# FTDI_USB_UART.net
KiCad netlist of a schematic drawn in Altium Designer
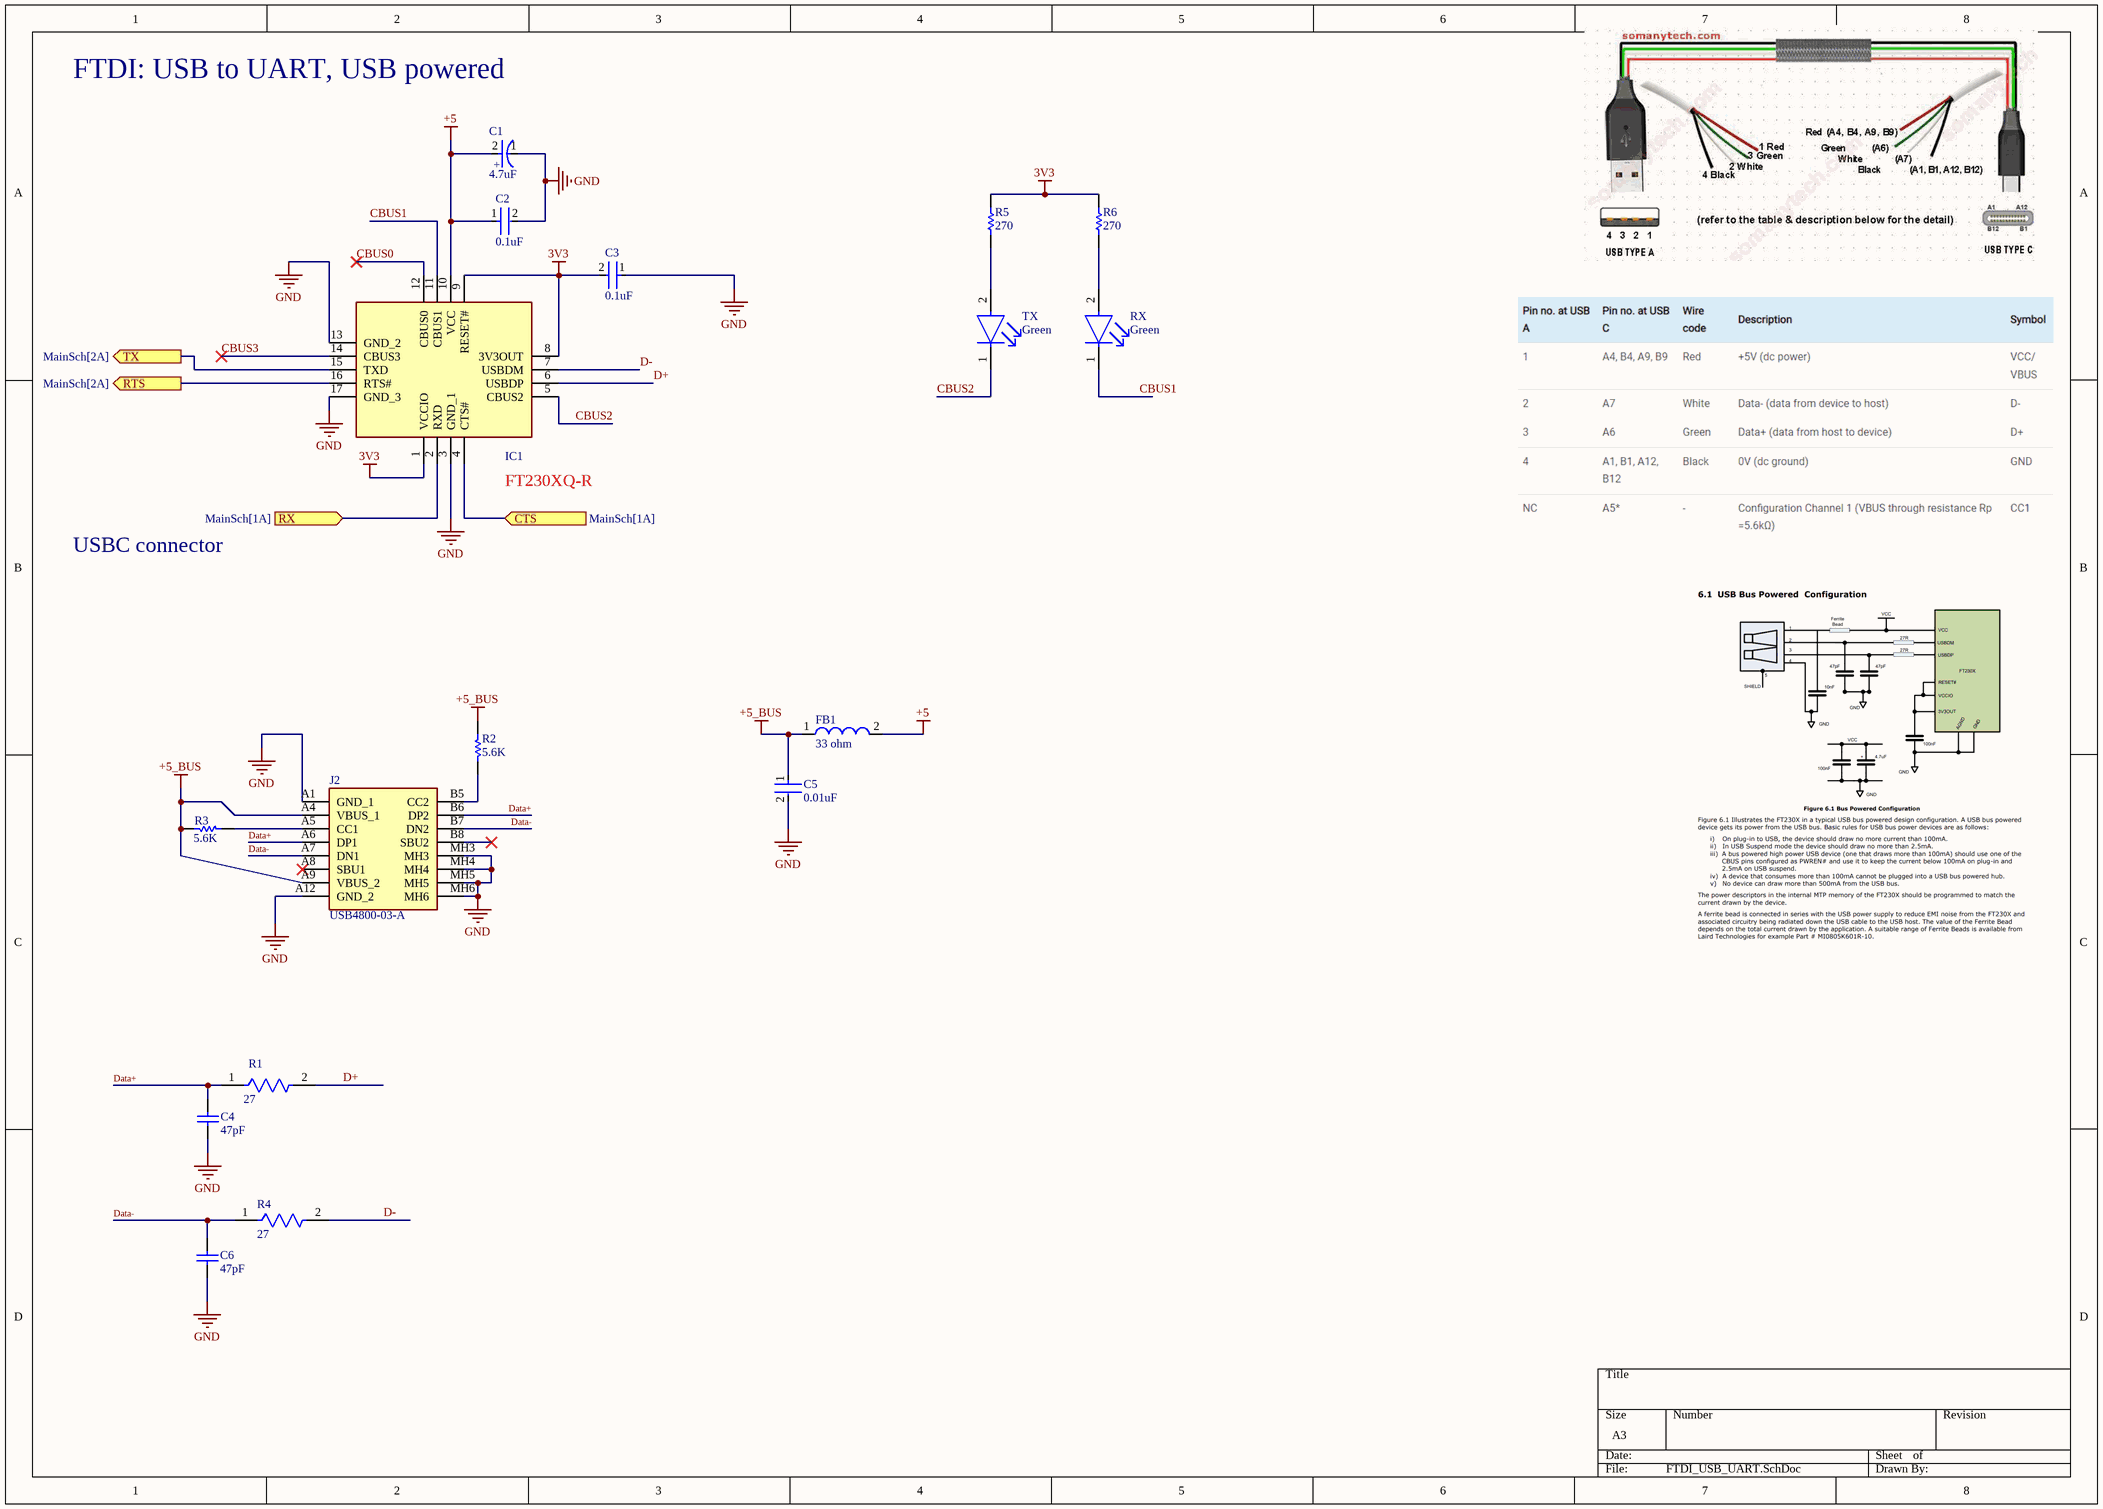
[diagram p0: FTDI_USB_UART.SchDoc]

(export (version "E")
  (design (tool "Eeschema 10.0.6"))
  (components
    (comp (ref "C1")
      (value "4.7uF")
      (footprint "FP-RAD-TH-D_6_3_0_5-L_11-MFG")
      (description "Aluminum Electrolytic Capacitors (Radial Lead Type) 4.7uF ±20% 160V")
      (fields (field (name "VOLTAGE") "160V") (field (name "TOLERANCE") "20%"))
      (libsource (lib "Altium Content Vault") (part "203bc49f2ac43e59fd269a8c329ed05"))
    )
    (comp (ref "C2")
      (value "0.1uF")
      (footprint "FP-C0603C-CF-MFG")
      (description "CAP CER 0.1UF 50V X7R 0603")
      (fields (field (name "TOLERANCE") "0.1") (field (name "MANUFACTURER") "KEMET"))
      (libsource (lib "Altium Content Vault") (part "b4654b650e69147ec39a6b967a45e02"))
    )
    (comp (ref "C3")
      (value "0.1uF")
      (footprint "FP-C0603C-CF-MFG")
      (description "CAP CER 0.1UF 50V X7R 0603")
      (fields (field (name "TOLERANCE") "0.1") (field (name "MANUFACTURER") "KEMET"))
      (libsource (lib "Altium Content Vault") (part "b4654b650e69147ec39a6b967a45e02"))
    )
    (comp (ref "C4")
      (value "47pF")
      (footprint "CAPC1608X90X35NL10T15")
      (fields (field (name "MANUFACTURER") "Murata") (field (name "PART NUMBER") "GRM1885C1H470JA01D"))
      (libsource (lib "Altium Content Vault") (part "CAP"))
    )
    (comp (ref "C5")
      (value "0.01uF")
      (footprint "FP-CC0603-DA-MFG")
      (description "CAP CER 10000PF 50V X7R 0603")
      (fields (field (name "TOLERANCE") "0.1") (field (name "MANUFACTURER PART NUMBER") "CC0603KRX7R9BB103"))
      (libsource (lib "Altium Content Vault") (part "11868f565c42a9108669ba33697ecf6"))
    )
    (comp (ref "C6")
      (value "47pF")
      (footprint "CAPC1608X90X35NL10T15")
      (fields (field (name "MANUFACTURER") "Murata") (field (name "PART NUMBER") "GRM1885C1H470JA01D"))
      (libsource (lib "Altium Content Vault") (part "CAP"))
    )
    (comp (ref "FB1")
      (value "33 ohm")
      (footprint "SMD-0805")
      (description "SMD EMI Suppression Ferrite Bead WE-CBF, Z = 33 Ohm")
      (libsource (lib "Altium Content Vault") (part "PAS-IND-INDUCTOR-2"))
    )
    (comp (ref "IC1")
      (value "FT230XQ-R")
      (footprint "SamacSys:QFN65P400X400X80-17N")
      (description "Integrated Circuit")
      (fields (field (name "MOUSER PART NUMBER") "895-FT230XQ-R"))
      (libsource (lib "*") (part "FT230XQ-R"))
    )
    (comp (ref "J2")
      (value "USB4800-03-A")
      (footprint "SamacSys:USB480003A")
      (description "Connector")
      (fields (field (name "MOUSER PART NUMBER") "640-USB4800-03-A"))
      (libsource (lib "SamacSys") (part "USB4800-03-A"))
    )
    (comp (ref "R1")
      (value "27")
      (footprint "FP-ERJ3EK-IPC_B")
      (description "RES SMD 27 OHM 1% 1/10W 0603")
      (fields (field (name "TOLERANCE") "1%"))
      (libsource (lib "Altium Content Vault") (part "1029c3af85768c4190bb7ad29bc67b5"))
    )
    (comp (ref "R2")
      (value "5.6K")
      (footprint "RESC1609X50X30NL10T20")
      (fields (field (name "PART NUMBER") "CRCW060356K0FKEA") (field (name "MANUFACTURER") "Vishay Dale"))
      (libsource (lib "Altium Content Vault") (part "RES"))
    )
    (comp (ref "R3")
      (value "5.6K")
      (footprint "RESC1609X50X30NL10T20")
      (fields (field (name "PART NUMBER") "CRCW060356K0FKEA") (field (name "MANUFACTURER") "Vishay Dale"))
      (libsource (lib "Altium Content Vault") (part "RES"))
    )
    (comp (ref "R4")
      (value "27")
      (footprint "FP-ERJ3EK-IPC_B")
      (description "RES SMD 27 OHM 1% 1/10W 0603")
      (fields (field (name "TOLERANCE") "1%"))
      (libsource (lib "Altium Content Vault") (part "1029c3af85768c4190bb7ad29bc67b5"))
    )
    (comp (ref "R5")
      (value "270")
      (footprint "RESC1609X50X30NL10T20")
      (fields (field (name "PART NUMBER") "CRCW060356K0FKEA") (field (name "MANUFACTURER") "Vishay Dale"))
      (libsource (lib "Altium Content Vault") (part "RES"))
    )
    (comp (ref "R6")
      (value "270")
      (footprint "RESC1609X50X30NL10T20")
      (fields (field (name "PART NUMBER") "CRCW060356K0FKEA") (field (name "MANUFACTURER") "Vishay Dale"))
      (libsource (lib "Altium Content Vault") (part "RES"))
    )
    (comp (ref "RX")
      (value "Green")
      (footprint "FP-150080SS75000-MFG")
      (description "LED RED CLEAR 0805 SMD")
      (libsource (lib "Altium Content Vault") (part "8706943c75ba83719d021d2fdc84c58"))
    )
    (comp (ref "TX")
      (value "Green")
      (footprint "FP-150080SS75000-MFG")
      (description "LED RED CLEAR 0805 SMD")
      (libsource (lib "Altium Content Vault") (part "8706943c75ba83719d021d2fdc84c58"))
    )
  )
  (nets
    (net (code "1") (name "+5") (class "Default")
      (node (ref "C1") (pin "2") (pinfunction "A_2") (pintype "passive"))
      (node (ref "C2") (pin "1") (pinfunction "1_1") (pintype "passive"))
      (node (ref "FB1") (pin "2") (pinfunction "2_2") (pintype "passive"))
      (node (ref "IC1") (pin "10") (pinfunction "VCC_10") (pintype "passive"))
    )
    (net (code "2") (name "+5_BUS") (class "Default")
      (node (ref "C5") (pin "1") (pinfunction "1_1") (pintype "passive"))
      (node (ref "FB1") (pin "1") (pinfunction "1_1") (pintype "passive"))
      (node (ref "J2") (pin "A4") (pinfunction "VBUS_1_A4") (pintype "passive"))
      (node (ref "J2") (pin "A9") (pinfunction "VBUS_2_A9") (pintype "passive"))
      (node (ref "R2") (pin "1") (pinfunction "1_1") (pintype "passive"))
      (node (ref "R3") (pin "2") (pinfunction "2_2") (pintype "passive"))
    )
    (net (code "3") (name "/CBUS0") (class "Default")
      (node (ref "IC1") (pin "12") (pinfunction "CBUS0_12") (pintype "passive+no_connect"))
    )
    (net (code "4") (name "/CBUS1") (class "Default")
      (node (ref "IC1") (pin "11") (pinfunction "CBUS1_11") (pintype "passive"))
      (node (ref "RX") (pin "1") (pinfunction "C_1") (pintype "passive"))
    )
    (net (code "5") (name "/CBUS2") (class "Default")
      (node (ref "IC1") (pin "5") (pinfunction "CBUS2_5") (pintype "passive"))
      (node (ref "TX") (pin "1") (pinfunction "C_1") (pintype "passive"))
    )
    (net (code "6") (name "/CBUS3") (class "Default")
      (node (ref "IC1") (pin "14") (pinfunction "CBUS3_14") (pintype "passive+no_connect"))
    )
    (net (code "7") (name "/CTS") (class "Default")
      (node (ref "IC1") (pin "4") (pinfunction "CTS#_4") (pintype "passive"))
    )
    (net (code "8") (name "/D+") (class "Default")
      (node (ref "IC1") (pin "6") (pinfunction "USBDP_6") (pintype "passive"))
      (node (ref "R1") (pin "2") (pinfunction "2_2") (pintype "passive"))
    )
    (net (code "9") (name "/D-") (class "Default")
      (node (ref "IC1") (pin "7") (pinfunction "USBDM_7") (pintype "passive"))
      (node (ref "R4") (pin "2") (pinfunction "2_2") (pintype "passive"))
    )
    (net (code "10") (name "/Data+") (class "Default")
      (node (ref "C4") (pin "2") (pinfunction "2_2") (pintype "passive"))
      (node (ref "J2") (pin "A6") (pinfunction "DP1_A6") (pintype "passive"))
      (node (ref "J2") (pin "B6") (pinfunction "DP2_B6") (pintype "passive"))
      (node (ref "R1") (pin "1") (pinfunction "1_1") (pintype "passive"))
    )
    (net (code "11") (name "/Data-") (class "Default")
      (node (ref "C6") (pin "2") (pinfunction "2_2") (pintype "passive"))
      (node (ref "J2") (pin "A7") (pinfunction "DN1_A7") (pintype "passive"))
      (node (ref "J2") (pin "B7") (pinfunction "DN2_B7") (pintype "passive"))
      (node (ref "R4") (pin "1") (pinfunction "1_1") (pintype "passive"))
    )
    (net (code "12") (name "/RTS") (class "Default")
      (node (ref "IC1") (pin "16") (pinfunction "RTS#_16") (pintype "passive"))
    )
    (net (code "13") (name "/RX") (class "Default")
      (node (ref "IC1") (pin "2") (pinfunction "RXD_2") (pintype "passive"))
    )
    (net (code "14") (name "/TX") (class "Default")
      (node (ref "IC1") (pin "15") (pinfunction "TXD_15") (pintype "passive"))
    )
    (net (code "15") (name "3V3") (class "Default")
      (node (ref "C3") (pin "2") (pinfunction "2_2") (pintype "passive"))
      (node (ref "IC1") (pin "1") (pinfunction "VCCIO_1") (pintype "passive"))
      (node (ref "IC1") (pin "8") (pinfunction "3V3OUT_8") (pintype "passive"))
      (node (ref "IC1") (pin "9") (pinfunction "RESET#_9") (pintype "passive"))
      (node (ref "R5") (pin "2") (pinfunction "2_2") (pintype "passive"))
      (node (ref "R6") (pin "2") (pinfunction "2_2") (pintype "passive"))
    )
    (net (code "16") (name "GND") (class "Default")
      (node (ref "C1") (pin "1") (pinfunction "C_1") (pintype "passive"))
      (node (ref "C2") (pin "2") (pinfunction "2_2") (pintype "passive"))
      (node (ref "C3") (pin "1") (pinfunction "1_1") (pintype "passive"))
      (node (ref "C4") (pin "1") (pinfunction "1_1") (pintype "passive"))
      (node (ref "C5") (pin "2") (pinfunction "2_2") (pintype "passive"))
      (node (ref "C6") (pin "1") (pinfunction "1_1") (pintype "passive"))
      (node (ref "IC1") (pin "13") (pinfunction "GND_2_13") (pintype "passive"))
      (node (ref "IC1") (pin "17") (pinfunction "GND_3_17") (pintype "passive"))
      (node (ref "IC1") (pin "3") (pinfunction "GND_1_3") (pintype "passive"))
      (node (ref "J2") (pin "A1") (pinfunction "GND_1_A1") (pintype "passive"))
      (node (ref "J2") (pin "A12") (pinfunction "GND_2_A12") (pintype "passive"))
      (node (ref "J2") (pin "MH3") (pinfunction "MH3_MH3") (pintype "passive"))
      (node (ref "J2") (pin "MH4") (pinfunction "MH4_MH4") (pintype "passive"))
      (node (ref "J2") (pin "MH5") (pinfunction "MH5_MH5") (pintype "passive"))
      (node (ref "J2") (pin "MH6") (pinfunction "MH6_MH6") (pintype "passive"))
    )
    (net (code "17") (name "Net-(J2-CC1)") (class "Default")
      (node (ref "J2") (pin "A5") (pinfunction "CC1_A5") (pintype "passive"))
      (node (ref "R3") (pin "1") (pinfunction "1_1") (pintype "passive"))
    )
    (net (code "18") (name "Net-(J2-CC2)") (class "Default")
      (node (ref "J2") (pin "B5") (pinfunction "CC2_B5") (pintype "passive"))
      (node (ref "R2") (pin "2") (pinfunction "2_2") (pintype "passive"))
    )
    (net (code "19") (name "Net-(RX-A)") (class "Default")
      (node (ref "R6") (pin "1") (pinfunction "1_1") (pintype "passive"))
      (node (ref "RX") (pin "2") (pinfunction "A_2") (pintype "passive"))
    )
    (net (code "20") (name "Net-(TX-A)") (class "Default")
      (node (ref "R5") (pin "1") (pinfunction "1_1") (pintype "passive"))
      (node (ref "TX") (pin "2") (pinfunction "A_2") (pintype "passive"))
    )
    (net (code "21") (name "unconnected-(J2-SBU1-PadA8)") (class "Default")
      (node (ref "J2") (pin "A8") (pinfunction "SBU1_A8") (pintype "passive+no_connect"))
    )
    (net (code "22") (name "unconnected-(J2-SBU2-PadB8)") (class "Default")
      (node (ref "J2") (pin "B8") (pinfunction "SBU2_B8") (pintype "passive+no_connect"))
    )
  )
)
